# recieving_end_copy.net
KiCad netlist of a schematic drawn in EAGLE
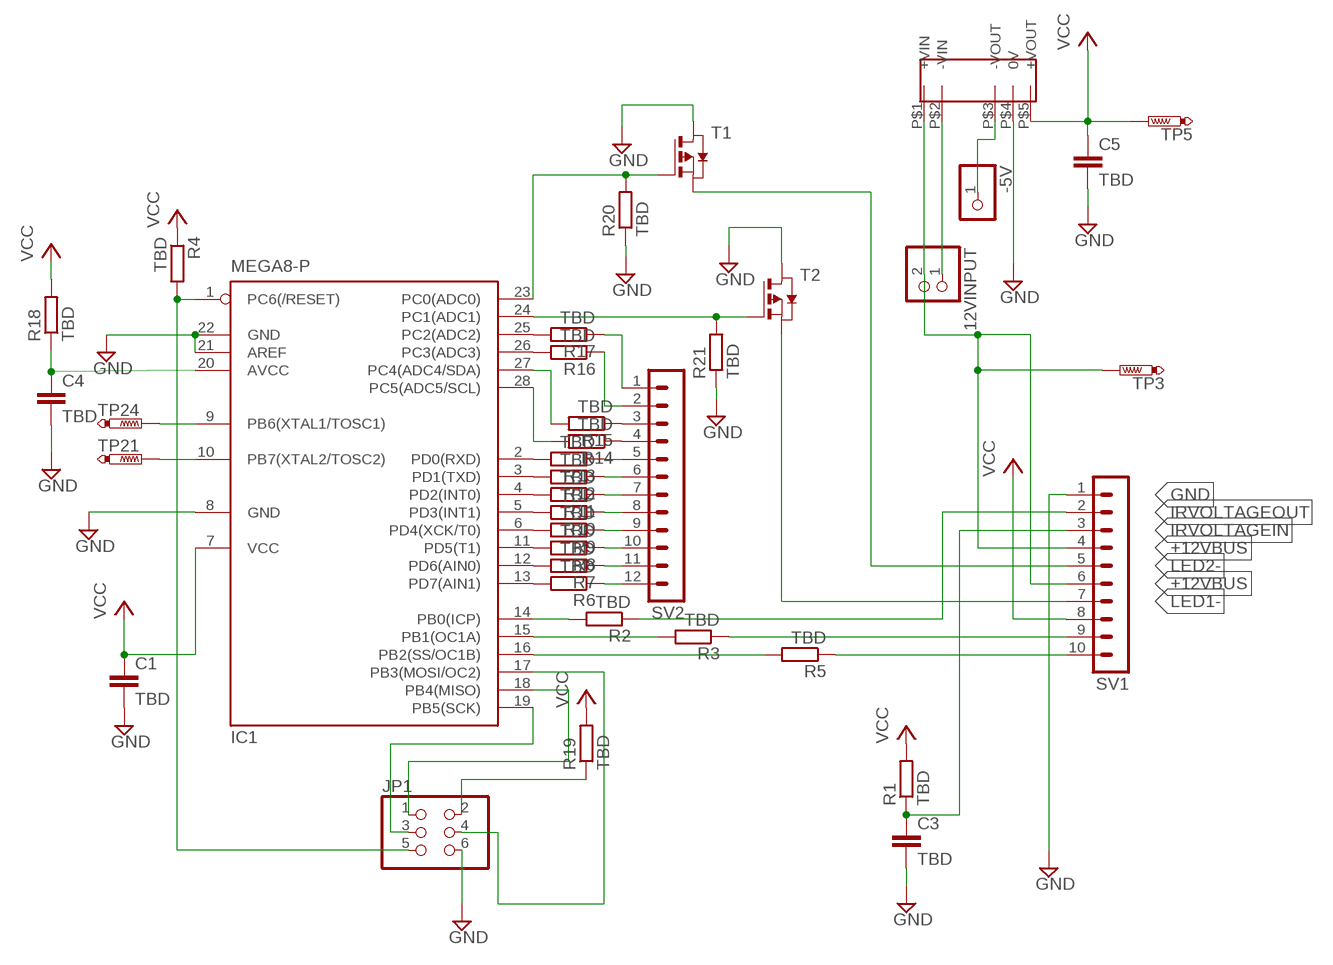
[diagram p0: schematic, sheet 1]

(export (version "E")
  (design (tool "Eeschema 10.0.6"))
  (components
    (comp (ref "-5V")
      (value "PINHD-1X1")
      (footprint "eagle-import:1X01")
      (libsource (lib "eagle-import") (part "PINHD-1X1"))
    )
    (comp (ref "12VINPUT")
      (value "PINHD-1X2")
      (footprint "eagle-import:1X02")
      (libsource (lib "eagle-import") (part "PINHD-1X2"))
    )
    (comp (ref "C1")
      (value "TBD")
      (footprint "eagle-import:C0805")
      (libsource (lib "eagle-import") (part "C-EUC0805"))
    )
    (comp (ref "C3")
      (value "TBD")
      (footprint "eagle-import:C0805")
      (libsource (lib "eagle-import") (part "C-EUC0805"))
    )
    (comp (ref "C4")
      (value "TBD")
      (footprint "eagle-import:C0805")
      (libsource (lib "eagle-import") (part "C-EUC0805"))
    )
    (comp (ref "C5")
      (value "TBD")
      (footprint "eagle-import:C0805")
      (libsource (lib "eagle-import") (part "C-EUC0805"))
    )
    (comp (ref "IC1")
      (value "MEGA8-P")
      (footprint "eagle-import:DIL28-3")
      (libsource (lib "eagle-import") (part "MEGA8-P"))
    )
    (comp (ref "JP1")
      (value "PINHD-2X3")
      (footprint "eagle-import:2X03")
      (libsource (lib "eagle-import") (part "PINHD-2X3"))
    )
    (comp (ref "R1")
      (value "TBD")
      (footprint "eagle-import:R0805")
      (libsource (lib "eagle-import") (part "R-EU_R0805"))
    )
    (comp (ref "R2")
      (value "TBD")
      (footprint "eagle-import:R0805")
      (libsource (lib "eagle-import") (part "R-EU_R0805"))
    )
    (comp (ref "R3")
      (value "TBD")
      (footprint "eagle-import:R0805")
      (libsource (lib "eagle-import") (part "R-EU_R0805"))
    )
    (comp (ref "R4")
      (value "TBD")
      (footprint "eagle-import:R0805")
      (libsource (lib "eagle-import") (part "R-EU_R0805"))
    )
    (comp (ref "R5")
      (value "TBD")
      (footprint "eagle-import:R0805")
      (libsource (lib "eagle-import") (part "R-EU_R0805"))
    )
    (comp (ref "R6")
      (value "TBD")
      (footprint "eagle-import:R0805")
      (libsource (lib "eagle-import") (part "R-EU_R0805"))
    )
    (comp (ref "R7")
      (value "TBD")
      (footprint "eagle-import:R0805")
      (libsource (lib "eagle-import") (part "R-EU_R0805"))
    )
    (comp (ref "R8")
      (value "TBD")
      (footprint "eagle-import:R0805")
      (libsource (lib "eagle-import") (part "R-EU_R0805"))
    )
    (comp (ref "R9")
      (value "TBD")
      (footprint "eagle-import:R0805")
      (libsource (lib "eagle-import") (part "R-EU_R0805"))
    )
    (comp (ref "R10")
      (value "TBD")
      (footprint "eagle-import:R0805")
      (libsource (lib "eagle-import") (part "R-EU_R0805"))
    )
    (comp (ref "R11")
      (value "TBD")
      (footprint "eagle-import:R0805")
      (libsource (lib "eagle-import") (part "R-EU_R0805"))
    )
    (comp (ref "R12")
      (value "TBD")
      (footprint "eagle-import:R0805")
      (libsource (lib "eagle-import") (part "R-EU_R0805"))
    )
    (comp (ref "R13")
      (value "TBD")
      (footprint "eagle-import:R0805")
      (libsource (lib "eagle-import") (part "R-EU_R0805"))
    )
    (comp (ref "R14")
      (value "TBD")
      (footprint "eagle-import:R0805")
      (libsource (lib "eagle-import") (part "R-EU_R0805"))
    )
    (comp (ref "R15")
      (value "TBD")
      (footprint "eagle-import:R0805")
      (libsource (lib "eagle-import") (part "R-EU_R0805"))
    )
    (comp (ref "R16")
      (value "TBD")
      (footprint "eagle-import:R0805")
      (libsource (lib "eagle-import") (part "R-EU_R0805"))
    )
    (comp (ref "R17")
      (value "TBD")
      (footprint "eagle-import:R0805")
      (libsource (lib "eagle-import") (part "R-EU_R0805"))
    )
    (comp (ref "R18")
      (value "TBD")
      (footprint "eagle-import:R0805")
      (libsource (lib "eagle-import") (part "R-EU_R0805"))
    )
    (comp (ref "R19")
      (value "TBD")
      (footprint "eagle-import:R0805")
      (libsource (lib "eagle-import") (part "R-EU_R0805"))
    )
    (comp (ref "R20")
      (value "TBD")
      (footprint "eagle-import:R0805")
      (libsource (lib "eagle-import") (part "R-EU_R0805"))
    )
    (comp (ref "R21")
      (value "TBD")
      (footprint "eagle-import:R0805")
      (libsource (lib "eagle-import") (part "R-EU_R0805"))
    )
    (comp (ref "SV1")
      (value "MA10-1")
      (footprint "eagle-import:MA10-1")
      (libsource (lib "eagle-import") (part "MA10-1"))
    )
    (comp (ref "SV2")
      (value "MA12-1")
      (footprint "eagle-import:MA12-1")
      (libsource (lib "eagle-import") (part "MA12-1"))
    )
    (comp (ref "T1")
      (value "PMOSSOT23ZXM61P02FTA")
      (footprint "eagle-import:SOT-23")
      (libsource (lib "eagle-import") (part "PMOSSOT23ZXM61P02FTA"))
    )
    (comp (ref "T2")
      (value "PMOSSOT23ZXM61P02FTA")
      (footprint "eagle-import:SOT-23")
      (libsource (lib "eagle-import") (part "PMOSSOT23ZXM61P02FTA"))
    )
    (comp (ref "TP3")
      (value "PTR1B1,27")
      (footprint "eagle-import:B1,27")
      (libsource (lib "eagle-import") (part "PTR1B1,27"))
    )
    (comp (ref "TP5")
      (value "PTR1B1,27")
      (footprint "eagle-import:B1,27")
      (libsource (lib "eagle-import") (part "PTR1B1,27"))
    )
    (comp (ref "TP21")
      (value "PTR1B1,27")
      (footprint "eagle-import:B1,27")
      (libsource (lib "eagle-import") (part "PTR1B1,27"))
    )
    (comp (ref "TP24")
      (value "PTR1B1,27")
      (footprint "eagle-import:B1,27")
      (libsource (lib "eagle-import") (part "PTR1B1,27"))
    )
    (comp (ref "U$1")
      (value "NKA1205SC")
      (footprint "eagle-import:NKA1205SC")
      (libsource (lib "eagle-import") (part "NKA1205SC"))
    )
  )
  (nets
    (net (code "1") (name "+12VBUS") (class "Default")
      (node (ref "12VINPUT") (pin "2") (pinfunction "2_2") (pintype "passive"))
      (node (ref "SV1") (pin "4") (pinfunction "4_4") (pintype "passive"))
      (node (ref "SV1") (pin "6") (pinfunction "6_6") (pintype "passive"))
      (node (ref "TP3") (pin "TP") (pinfunction "TP_TP") (pintype "input"))
      (node (ref "U$1") (pin "P$1") (pinfunction "+VIN_P$1") (pintype "bidirectional"))
    )
    (net (code "2") (name "GND") (class "Default")
      (node (ref "C1") (pin "2") (pinfunction "2_2") (pintype "passive"))
      (node (ref "C3") (pin "2") (pinfunction "2_2") (pintype "passive"))
      (node (ref "C4") (pin "2") (pinfunction "2_2") (pintype "passive"))
      (node (ref "C5") (pin "2") (pinfunction "2_2") (pintype "passive"))
      (node (ref "IC1") (pin "21") (pinfunction "AREF_21") (pintype "passive"))
      (node (ref "IC1") (pin "22") (pinfunction "GND_22") (pintype "power_in"))
      (node (ref "IC1") (pin "8") (pinfunction "GND_8") (pintype "power_in"))
      (node (ref "JP1") (pin "6") (pinfunction "6_6") (pintype "passive"))
      (node (ref "R20") (pin "1") (pinfunction "1_1") (pintype "passive"))
      (node (ref "R21") (pin "1") (pinfunction "1_1") (pintype "passive"))
      (node (ref "SV1") (pin "1") (pinfunction "1_1") (pintype "passive"))
      (node (ref "T1") (pin "1") (pinfunction "D_1") (pintype "passive"))
      (node (ref "T2") (pin "1") (pinfunction "D_1") (pintype "passive"))
      (node (ref "U$1") (pin "P$4") (pinfunction "0V_P$4") (pintype "bidirectional"))
    )
    (net (code "3") (name "IRVOLTAGEIN") (class "Default")
      (node (ref "C3") (pin "1") (pinfunction "1_1") (pintype "passive"))
      (node (ref "R1") (pin "1") (pinfunction "1_1") (pintype "passive"))
      (node (ref "SV1") (pin "3") (pinfunction "3_3") (pintype "passive"))
    )
    (net (code "4") (name "IRVOLTAGEOUT") (class "Default")
      (node (ref "R2") (pin "1") (pinfunction "1_1") (pintype "passive"))
      (node (ref "SV1") (pin "2") (pinfunction "2_2") (pintype "passive"))
    )
    (net (code "5") (name "LED1-") (class "Default")
      (node (ref "SV1") (pin "7") (pinfunction "7_7") (pintype "passive"))
      (node (ref "T2") (pin "2") (pinfunction "S_2") (pintype "passive"))
    )
    (net (code "6") (name "LED2-") (class "Default")
      (node (ref "SV1") (pin "5") (pinfunction "5_5") (pintype "passive"))
      (node (ref "T1") (pin "2") (pinfunction "S_2") (pintype "passive"))
    )
    (net (code "7") (name "Net-(IC1-AVCC)") (class "Default")
      (node (ref "C4") (pin "1") (pinfunction "1_1") (pintype "passive"))
      (node (ref "IC1") (pin "20") (pinfunction "AVCC_20") (pintype "power_in"))
      (node (ref "R18") (pin "1") (pinfunction "1_1") (pintype "passive"))
    )
    (net (code "8") (name "Net-(IC1-PB0(ICP))") (class "Default")
      (node (ref "IC1") (pin "14") (pinfunction "PB0(ICP)_14") (pintype "bidirectional"))
      (node (ref "R2") (pin "2") (pinfunction "2_2") (pintype "passive"))
    )
    (net (code "9") (name "Net-(IC1-PB1(OC1A))") (class "Default")
      (node (ref "IC1") (pin "15") (pinfunction "PB1(OC1A)_15") (pintype "bidirectional"))
      (node (ref "R3") (pin "2") (pinfunction "2_2") (pintype "passive"))
    )
    (net (code "10") (name "Net-(IC1-PB2(SS{slash}OC1B))") (class "Default")
      (node (ref "IC1") (pin "16") (pinfunction "PB2(SS/OC1B)_16") (pintype "bidirectional"))
      (node (ref "R5") (pin "2") (pinfunction "2_2") (pintype "passive"))
    )
    (net (code "11") (name "Net-(IC1-PB3(MOSI{slash}OC2))") (class "Default")
      (node (ref "IC1") (pin "17") (pinfunction "PB3(MOSI/OC2)_17") (pintype "bidirectional"))
      (node (ref "JP1") (pin "4") (pinfunction "4_4") (pintype "passive"))
    )
    (net (code "12") (name "Net-(IC1-PB4(MISO))") (class "Default")
      (node (ref "IC1") (pin "18") (pinfunction "PB4(MISO)_18") (pintype "bidirectional"))
      (node (ref "JP1") (pin "1") (pinfunction "1_1") (pintype "passive"))
    )
    (net (code "13") (name "Net-(IC1-PB5(SCK))") (class "Default")
      (node (ref "IC1") (pin "19") (pinfunction "PB5(SCK)_19") (pintype "bidirectional"))
      (node (ref "JP1") (pin "3") (pinfunction "3_3") (pintype "passive"))
    )
    (net (code "14") (name "Net-(IC1-PB6(XTAL1{slash}TOSC1))") (class "Default")
      (node (ref "IC1") (pin "9") (pinfunction "PB6(XTAL1/TOSC1)_9") (pintype "bidirectional"))
      (node (ref "TP24") (pin "TP") (pinfunction "TP_TP") (pintype "input"))
    )
    (net (code "15") (name "Net-(IC1-PB7(XTAL2{slash}TOSC2))") (class "Default")
      (node (ref "IC1") (pin "10") (pinfunction "PB7(XTAL2/TOSC2)_10") (pintype "bidirectional"))
      (node (ref "TP21") (pin "TP") (pinfunction "TP_TP") (pintype "input"))
    )
    (net (code "16") (name "Net-(IC1-PC0(ADC0))") (class "Default")
      (node (ref "IC1") (pin "23") (pinfunction "PC0(ADC0)_23") (pintype "bidirectional"))
      (node (ref "R20") (pin "2") (pinfunction "2_2") (pintype "passive"))
      (node (ref "T1") (pin "3") (pinfunction "G_3") (pintype "passive"))
    )
    (net (code "17") (name "Net-(IC1-PC1(ADC1))") (class "Default")
      (node (ref "IC1") (pin "24") (pinfunction "PC1(ADC1)_24") (pintype "bidirectional"))
      (node (ref "R21") (pin "2") (pinfunction "2_2") (pintype "passive"))
      (node (ref "T2") (pin "3") (pinfunction "G_3") (pintype "passive"))
    )
    (net (code "18") (name "Net-(IC1-PC2(ADC2))") (class "Default")
      (node (ref "IC1") (pin "25") (pinfunction "PC2(ADC2)_25") (pintype "bidirectional"))
      (node (ref "R17") (pin "2") (pinfunction "2_2") (pintype "passive"))
    )
    (net (code "19") (name "Net-(IC1-PC3(ADC3))") (class "Default")
      (node (ref "IC1") (pin "26") (pinfunction "PC3(ADC3)_26") (pintype "bidirectional"))
      (node (ref "R16") (pin "2") (pinfunction "2_2") (pintype "passive"))
    )
    (net (code "20") (name "Net-(IC1-PC4(ADC4{slash}SDA))") (class "Default")
      (node (ref "IC1") (pin "27") (pinfunction "PC4(ADC4/SDA)_27") (pintype "bidirectional"))
      (node (ref "R15") (pin "2") (pinfunction "2_2") (pintype "passive"))
    )
    (net (code "21") (name "Net-(IC1-PC5(ADC5{slash}SCL))") (class "Default")
      (node (ref "IC1") (pin "28") (pinfunction "PC5(ADC5/SCL)_28") (pintype "bidirectional"))
      (node (ref "R14") (pin "2") (pinfunction "2_2") (pintype "passive"))
    )
    (net (code "22") (name "Net-(IC1-PC6({slash}RESET))") (class "Default")
      (node (ref "IC1") (pin "1") (pinfunction "PC6(/RESET)_1") (pintype "bidirectional"))
      (node (ref "JP1") (pin "5") (pinfunction "5_5") (pintype "passive"))
      (node (ref "R4") (pin "2") (pinfunction "2_2") (pintype "passive"))
    )
    (net (code "23") (name "Net-(IC1-PD0(RXD))") (class "Default")
      (node (ref "IC1") (pin "2") (pinfunction "PD0(RXD)_2") (pintype "bidirectional"))
      (node (ref "R13") (pin "2") (pinfunction "2_2") (pintype "passive"))
    )
    (net (code "24") (name "Net-(IC1-PD1(TXD))") (class "Default")
      (node (ref "IC1") (pin "3") (pinfunction "PD1(TXD)_3") (pintype "bidirectional"))
      (node (ref "R12") (pin "2") (pinfunction "2_2") (pintype "passive"))
    )
    (net (code "25") (name "Net-(IC1-PD2(INT0))") (class "Default")
      (node (ref "IC1") (pin "4") (pinfunction "PD2(INT0)_4") (pintype "bidirectional"))
      (node (ref "R11") (pin "2") (pinfunction "2_2") (pintype "passive"))
    )
    (net (code "26") (name "Net-(IC1-PD3(INT1))") (class "Default")
      (node (ref "IC1") (pin "5") (pinfunction "PD3(INT1)_5") (pintype "bidirectional"))
      (node (ref "R10") (pin "2") (pinfunction "2_2") (pintype "passive"))
    )
    (net (code "27") (name "Net-(IC1-PD4(XCK{slash}T0))") (class "Default")
      (node (ref "IC1") (pin "6") (pinfunction "PD4(XCK/T0)_6") (pintype "bidirectional"))
      (node (ref "R9") (pin "2") (pinfunction "2_2") (pintype "passive"))
    )
    (net (code "28") (name "Net-(IC1-PD5(T1))") (class "Default")
      (node (ref "IC1") (pin "11") (pinfunction "PD5(T1)_11") (pintype "bidirectional"))
      (node (ref "R8") (pin "2") (pinfunction "2_2") (pintype "passive"))
    )
    (net (code "29") (name "Net-(IC1-PD6(AIN0))") (class "Default")
      (node (ref "IC1") (pin "12") (pinfunction "PD6(AIN0)_12") (pintype "bidirectional"))
      (node (ref "R7") (pin "2") (pinfunction "2_2") (pintype "passive"))
    )
    (net (code "30") (name "Net-(IC1-PD7(AIN1))") (class "Default")
      (node (ref "IC1") (pin "13") (pinfunction "PD7(AIN1)_13") (pintype "bidirectional"))
      (node (ref "R6") (pin "2") (pinfunction "2_2") (pintype "passive"))
    )
    (net (code "31") (name "Net-(JP1-Pad2)") (class "Default")
      (node (ref "JP1") (pin "2") (pinfunction "2_2") (pintype "passive"))
      (node (ref "R19") (pin "1") (pinfunction "1_1") (pintype "passive"))
    )
    (net (code "32") (name "Net-(R3-Pad1)") (class "Default")
      (node (ref "R3") (pin "1") (pinfunction "1_1") (pintype "passive"))
      (node (ref "SV1") (pin "9") (pinfunction "9_9") (pintype "passive"))
    )
    (net (code "33") (name "Net-(R5-Pad1)") (class "Default")
      (node (ref "R5") (pin "1") (pinfunction "1_1") (pintype "passive"))
      (node (ref "SV1") (pin "10") (pinfunction "10_10") (pintype "passive"))
    )
    (net (code "34") (name "Net-(R6-Pad1)") (class "Default")
      (node (ref "R6") (pin "1") (pinfunction "1_1") (pintype "passive"))
      (node (ref "SV2") (pin "12") (pinfunction "12_12") (pintype "passive"))
    )
    (net (code "35") (name "Net-(R7-Pad1)") (class "Default")
      (node (ref "R7") (pin "1") (pinfunction "1_1") (pintype "passive"))
      (node (ref "SV2") (pin "11") (pinfunction "11_11") (pintype "passive"))
    )
    (net (code "36") (name "Net-(R8-Pad1)") (class "Default")
      (node (ref "R8") (pin "1") (pinfunction "1_1") (pintype "passive"))
      (node (ref "SV2") (pin "10") (pinfunction "10_10") (pintype "passive"))
    )
    (net (code "37") (name "Net-(R9-Pad1)") (class "Default")
      (node (ref "R9") (pin "1") (pinfunction "1_1") (pintype "passive"))
      (node (ref "SV2") (pin "9") (pinfunction "9_9") (pintype "passive"))
    )
    (net (code "38") (name "Net-(R10-Pad1)") (class "Default")
      (node (ref "R10") (pin "1") (pinfunction "1_1") (pintype "passive"))
      (node (ref "SV2") (pin "8") (pinfunction "8_8") (pintype "passive"))
    )
    (net (code "39") (name "Net-(R11-Pad1)") (class "Default")
      (node (ref "R11") (pin "1") (pinfunction "1_1") (pintype "passive"))
      (node (ref "SV2") (pin "7") (pinfunction "7_7") (pintype "passive"))
    )
    (net (code "40") (name "Net-(R12-Pad1)") (class "Default")
      (node (ref "R12") (pin "1") (pinfunction "1_1") (pintype "passive"))
      (node (ref "SV2") (pin "6") (pinfunction "6_6") (pintype "passive"))
    )
    (net (code "41") (name "Net-(R13-Pad1)") (class "Default")
      (node (ref "R13") (pin "1") (pinfunction "1_1") (pintype "passive"))
      (node (ref "SV2") (pin "5") (pinfunction "5_5") (pintype "passive"))
    )
    (net (code "42") (name "Net-(R14-Pad1)") (class "Default")
      (node (ref "R14") (pin "1") (pinfunction "1_1") (pintype "passive"))
      (node (ref "SV2") (pin "4") (pinfunction "4_4") (pintype "passive"))
    )
    (net (code "43") (name "Net-(R15-Pad1)") (class "Default")
      (node (ref "R15") (pin "1") (pinfunction "1_1") (pintype "passive"))
      (node (ref "SV2") (pin "3") (pinfunction "3_3") (pintype "passive"))
    )
    (net (code "44") (name "Net-(R16-Pad1)") (class "Default")
      (node (ref "R16") (pin "1") (pinfunction "1_1") (pintype "passive"))
      (node (ref "SV2") (pin "2") (pinfunction "2_2") (pintype "passive"))
    )
    (net (code "45") (name "Net-(R17-Pad1)") (class "Default")
      (node (ref "R17") (pin "1") (pinfunction "1_1") (pintype "passive"))
      (node (ref "SV2") (pin "1") (pinfunction "1_1") (pintype "passive"))
    )
    (net (code "46") (name "Net-(U$1--VIN)") (class "Default")
      (node (ref "12VINPUT") (pin "1") (pinfunction "1_1") (pintype "passive"))
      (node (ref "U$1") (pin "P$2") (pinfunction "-VIN_P$2") (pintype "bidirectional"))
    )
    (net (code "47") (name "Net-(U$1--VOUT)") (class "Default")
      (node (ref "-5V") (pin "1") (pinfunction "1_1") (pintype "passive"))
      (node (ref "U$1") (pin "P$3") (pinfunction "-VOUT_P$3") (pintype "bidirectional"))
    )
    (net (code "48") (name "VCC") (class "Default")
      (node (ref "C1") (pin "1") (pinfunction "1_1") (pintype "passive"))
      (node (ref "C5") (pin "1") (pinfunction "1_1") (pintype "passive"))
      (node (ref "IC1") (pin "7") (pinfunction "VCC_7") (pintype "power_in"))
      (node (ref "R1") (pin "2") (pinfunction "2_2") (pintype "passive"))
      (node (ref "R18") (pin "2") (pinfunction "2_2") (pintype "passive"))
      (node (ref "R19") (pin "2") (pinfunction "2_2") (pintype "passive"))
      (node (ref "R4") (pin "1") (pinfunction "1_1") (pintype "passive"))
      (node (ref "SV1") (pin "8") (pinfunction "8_8") (pintype "passive"))
      (node (ref "TP5") (pin "TP") (pinfunction "TP_TP") (pintype "input"))
      (node (ref "U$1") (pin "P$5") (pinfunction "+VOUT_P$5") (pintype "bidirectional"))
    )
  )
)
